# USB.net
KiCad netlist of a schematic drawn in Altium Designer
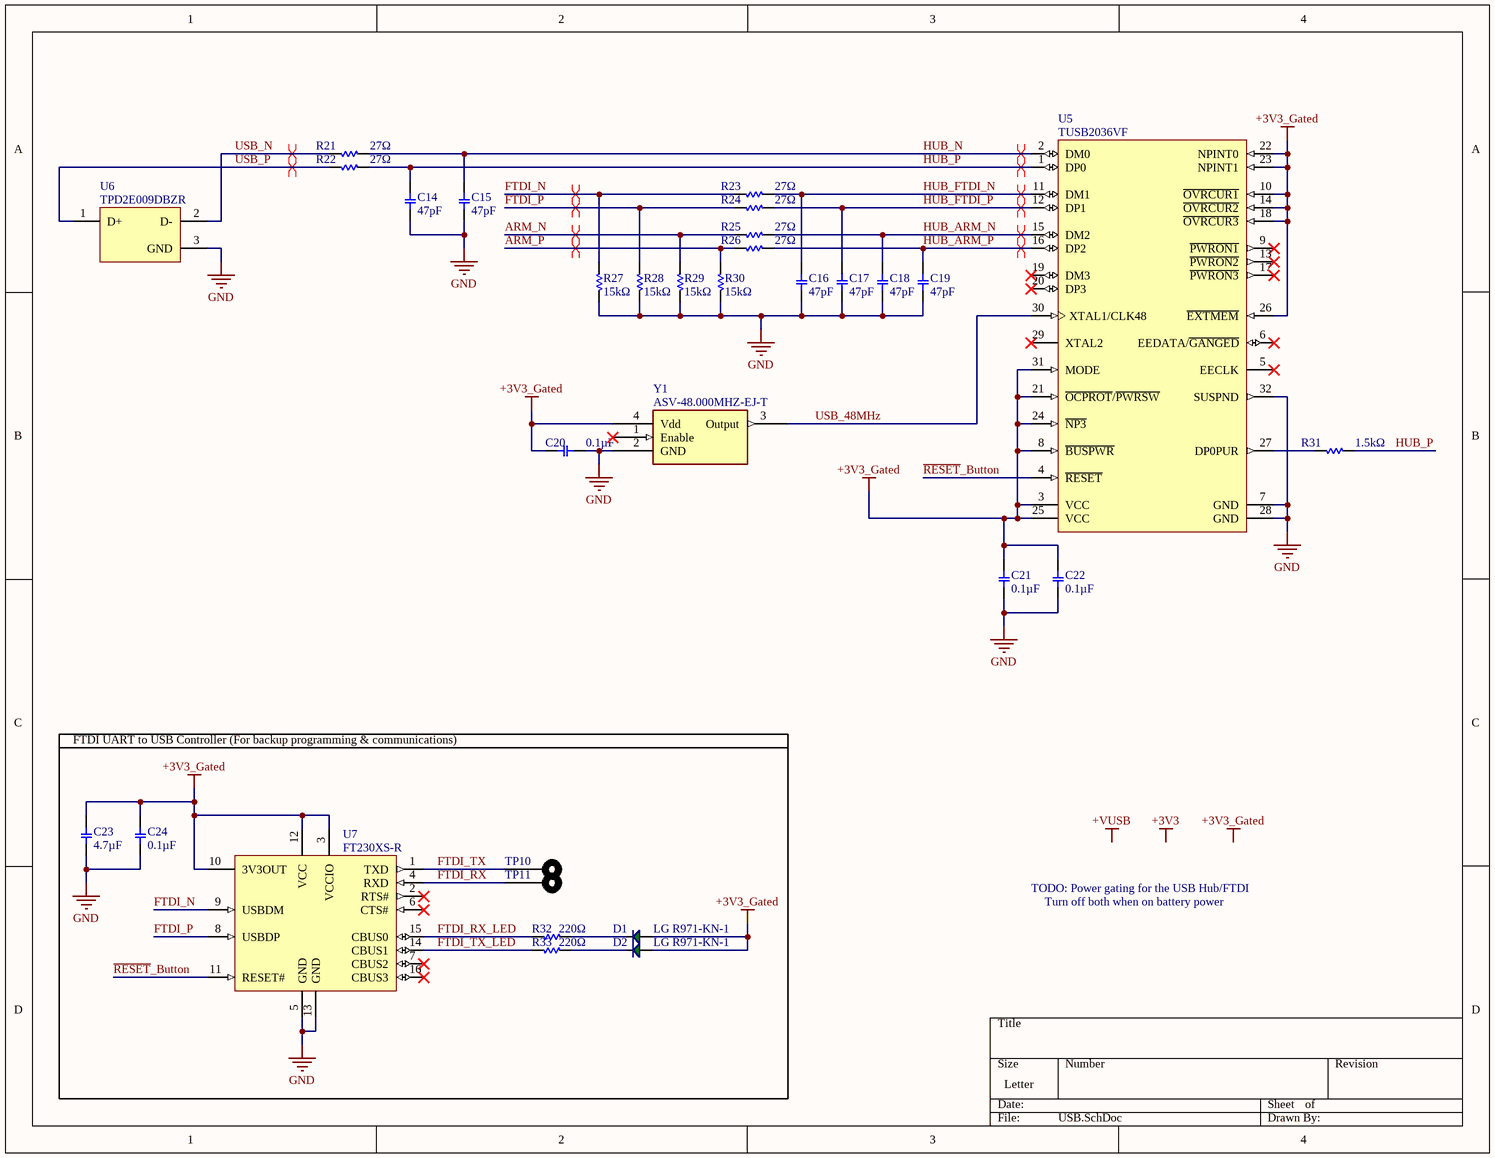
[diagram p0: USB.SchDoc]

(export (version "E")
  (design (tool "Eeschema 10.0.6"))
  (components
    (comp (ref "C14")
      (value "47pF")
      (footprint "C0805(2012)_NP_med")
      (description "SMT Capacitor")
      (fields (field (name "TOLERANCE") "X7R"))
      (libsource (lib "ChipComponents") (part "CPN_SMT"))
    )
    (comp (ref "C15")
      (value "47pF")
      (footprint "C0805(2012)_NP_med")
      (description "SMT Capacitor")
      (fields (field (name "TOLERANCE") "X7R"))
      (libsource (lib "ChipComponents") (part "CPN_SMT"))
    )
    (comp (ref "C16")
      (value "47pF")
      (footprint "C0805(2012)_NP_med")
      (description "SMT Capacitor")
      (fields (field (name "TOLERANCE") "X7R"))
      (libsource (lib "ChipComponents") (part "CPN_SMT"))
    )
    (comp (ref "C17")
      (value "47pF")
      (footprint "C0805(2012)_NP_med")
      (description "SMT Capacitor")
      (fields (field (name "TOLERANCE") "X7R"))
      (libsource (lib "ChipComponents") (part "CPN_SMT"))
    )
    (comp (ref "C18")
      (value "47pF")
      (footprint "C0805(2012)_NP_med")
      (description "SMT Capacitor")
      (fields (field (name "TOLERANCE") "X7R"))
      (libsource (lib "ChipComponents") (part "CPN_SMT"))
    )
    (comp (ref "C19")
      (value "47pF")
      (footprint "C0805(2012)_NP_med")
      (description "SMT Capacitor")
      (fields (field (name "TOLERANCE") "X7R"))
      (libsource (lib "ChipComponents") (part "CPN_SMT"))
    )
    (comp (ref "C20")
      (value "0.1µF")
      (footprint "C0805(2012)_NP_med")
      (description "SMT Capacitor")
      (fields (field (name "TOLERANCE") "X7R"))
      (libsource (lib "ChipComponents") (part "CPN_SMT"))
    )
    (comp (ref "C21")
      (value "0.1µF")
      (footprint "C0805(2012)_NP_med")
      (description "SMT Capacitor")
      (fields (field (name "TOLERANCE") "X7R"))
      (libsource (lib "ChipComponents") (part "CPN_SMT"))
    )
    (comp (ref "C22")
      (value "0.1µF")
      (footprint "C0805(2012)_NP_med")
      (description "SMT Capacitor")
      (fields (field (name "TOLERANCE") "X7R"))
      (libsource (lib "ChipComponents") (part "CPN_SMT"))
    )
    (comp (ref "C23")
      (value "4.7µF")
      (footprint "C0805(2012)_NP_med")
      (description "SMT Capacitor")
      (fields (field (name "TOLERANCE") "X7R"))
      (libsource (lib "ChipComponents") (part "CPN_SMT"))
    )
    (comp (ref "C24")
      (value "0.1µF")
      (footprint "C0805(2012)_NP_med")
      (description "SMT Capacitor")
      (fields (field (name "TOLERANCE") "X7R"))
      (libsource (lib "ChipComponents") (part "CPN_SMT"))
    )
    (comp (ref "D1")
      (value "LG R971-KN-1")
      (footprint "C0805(2012)_P_med")
      (description "SMT LED")
      (fields (field (name "MANUFACTURER") "AVX") (field (name "PART NUMBER") "SD0805S020S1R0"))
      (libsource (lib "ChipComponents") (part "DIODE_sMT"))
    )
    (comp (ref "D2")
      (value "LG R971-KN-1")
      (footprint "C0805(2012)_P_med")
      (description "SMT LED")
      (fields (field (name "MANUFACTURER") "AVX") (field (name "PART NUMBER") "SD0805S020S1R0"))
      (libsource (lib "ChipComponents") (part "DIODE_sMT"))
    )
    (comp (ref "R21")
      (value "27Ω")
      (footprint "R0805(2012)_med")
      (description "SMT resistor")
      (fields (field (name "TOLERANCE") "1%"))
      (libsource (lib "ChipComponents") (part "RES_SMT"))
    )
    (comp (ref "R22")
      (value "27Ω")
      (footprint "R0805(2012)_med")
      (description "SMT resistor")
      (fields (field (name "TOLERANCE") "1%"))
      (libsource (lib "ChipComponents") (part "RES_SMT"))
    )
    (comp (ref "R23")
      (value "27Ω")
      (footprint "R0805(2012)_med")
      (description "SMT resistor")
      (fields (field (name "TOLERANCE") "1%"))
      (libsource (lib "ChipComponents") (part "RES_SMT"))
    )
    (comp (ref "R24")
      (value "27Ω")
      (footprint "R0805(2012)_med")
      (description "SMT resistor")
      (fields (field (name "TOLERANCE") "1%"))
      (libsource (lib "ChipComponents") (part "RES_SMT"))
    )
    (comp (ref "R25")
      (value "27Ω")
      (footprint "R0805(2012)_med")
      (description "SMT resistor")
      (fields (field (name "TOLERANCE") "1%"))
      (libsource (lib "ChipComponents") (part "RES_SMT"))
    )
    (comp (ref "R26")
      (value "27Ω")
      (footprint "R0805(2012)_med")
      (description "SMT resistor")
      (fields (field (name "TOLERANCE") "1%"))
      (libsource (lib "ChipComponents") (part "RES_SMT"))
    )
    (comp (ref "R27")
      (value "15kΩ")
      (footprint "R0805(2012)_med")
      (description "SMT resistor")
      (fields (field (name "TOLERANCE") "1%"))
      (libsource (lib "ChipComponents") (part "RES_SMT"))
    )
    (comp (ref "R28")
      (value "15kΩ")
      (footprint "R0805(2012)_med")
      (description "SMT resistor")
      (fields (field (name "TOLERANCE") "1%"))
      (libsource (lib "ChipComponents") (part "RES_SMT"))
    )
    (comp (ref "R29")
      (value "15kΩ")
      (footprint "R0805(2012)_med")
      (description "SMT resistor")
      (fields (field (name "TOLERANCE") "1%"))
      (libsource (lib "ChipComponents") (part "RES_SMT"))
    )
    (comp (ref "R30")
      (value "15kΩ")
      (footprint "R0805(2012)_med")
      (description "SMT resistor")
      (fields (field (name "TOLERANCE") "1%"))
      (libsource (lib "ChipComponents") (part "RES_SMT"))
    )
    (comp (ref "R31")
      (value "1.5kΩ")
      (footprint "R0805(2012)_med")
      (description "SMT resistor")
      (fields (field (name "TOLERANCE") "1%"))
      (libsource (lib "ChipComponents") (part "RES_SMT"))
    )
    (comp (ref "R32")
      (value "220Ω")
      (footprint "R0805(2012)_med")
      (description "SMT resistor")
      (fields (field (name "TOLERANCE") "1%"))
      (libsource (lib "ChipComponents") (part "RES_SMT"))
    )
    (comp (ref "R33")
      (value "220Ω")
      (footprint "R0805(2012)_med")
      (description "SMT resistor")
      (fields (field (name "TOLERANCE") "1%"))
      (libsource (lib "ChipComponents") (part "RES_SMT"))
    )
    (comp (ref "TP10")
      (value "Testpoint")
      (footprint "TESTPOINT")
      (description "A single hole in the board")
      (libsource (lib "RFIDSchematicLibrary") (part "Testpoint"))
    )
    (comp (ref "TP11")
      (value "Testpoint")
      (footprint "TESTPOINT")
      (description "A single hole in the board")
      (libsource (lib "RFIDSchematicLibrary") (part "Testpoint"))
    )
    (comp (ref "U5")
      (value "TUSB2036VF")
      (footprint "VF32_M")
      (fields (field (name "MANUFACTURER") "Texas Instruments"))
      (libsource (lib "Texas Instruments Interface USB") (part "TUSB2036VF"))
    )
    (comp (ref "U6")
      (value "TPD2E009DBZR")
      (footprint "DBZ3_N")
      (fields (field (name "MANUFACTURER") "Texas Instruments"))
      (libsource (lib "TI Interface ESD EMI Protection") (part "TPD2E009DBZR"))
    )
    (comp (ref "U7")
      (value "FT230XS-R")
      (footprint "SSOP-16_M")
      (fields (field (name "MANUFACTURER") "FTDI"))
      (libsource (lib "FTDI FT-X Series") (part "FT230XS-R"))
    )
    (comp (ref "Y1")
      (value "ASV-48.000MHZ-EJ-T")
      (footprint "Abracon ASV XO")
      (description "OSC XO X.000MHZ HCMOS SMD")
      (libsource (lib "RFIDSchematicLibrary") (part "Abacrom ASV Series"))
    )
  )
  (nets
    (net (code "2") (name "+3V3_Gated") (class "Default")
      (node (ref "C20") (pin "1") (pinfunction "1_1") (pintype "passive"))
      (node (ref "C21") (pin "1") (pinfunction "1_1") (pintype "passive"))
      (node (ref "C22") (pin "1") (pinfunction "1_1") (pintype "passive"))
      (node (ref "C23") (pin "1") (pinfunction "1_1") (pintype "passive"))
      (node (ref "C24") (pin "1") (pinfunction "1_1") (pintype "passive"))
      (node (ref "D1") (pin "2") (pinfunction "A_2") (pintype "passive"))
      (node (ref "D2") (pin "2") (pinfunction "A_2") (pintype "passive"))
      (node (ref "U5") (pin "10") (pinfunction "~{OVRCUR1}_10") (pintype "input"))
      (node (ref "U5") (pin "14") (pinfunction "~{OVRCUR2}_14") (pintype "input"))
      (node (ref "U5") (pin "18") (pinfunction "~{OVRCUR3}_18") (pintype "input"))
      (node (ref "U5") (pin "21") (pinfunction "~{OCPROT}/~{PWRSW}_21") (pintype "input"))
      (node (ref "U5") (pin "22") (pinfunction "NPINT0_22") (pintype "input"))
      (node (ref "U5") (pin "23") (pinfunction "NPINT1_23") (pintype "input"))
      (node (ref "U5") (pin "24") (pinfunction "~{NP3}_24") (pintype "input"))
      (node (ref "U5") (pin "25") (pinfunction "VCC_25") (pintype "power_in"))
      (node (ref "U5") (pin "26") (pinfunction "~{EXTMEM}_26") (pintype "input"))
      (node (ref "U5") (pin "3") (pinfunction "VCC_3") (pintype "power_in"))
      (node (ref "U5") (pin "31") (pinfunction "MODE_31") (pintype "input"))
      (node (ref "U5") (pin "8") (pinfunction "~{BUSPWR}_8") (pintype "input"))
      (node (ref "U7") (pin "10") (pinfunction "3V3OUT_10") (pintype "power_in"))
      (node (ref "U7") (pin "12") (pinfunction "VCC_12") (pintype "power_in"))
      (node (ref "U7") (pin "3") (pinfunction "VCCIO_3") (pintype "power_in"))
      (node (ref "Y1") (pin "4") (pinfunction "Vdd_4") (pintype "power_in"))
    )
    (net (code "4") (name "/ARM_N") (class "Default")
      (node (ref "R25") (pin "1") (pinfunction "1_1") (pintype "passive"))
      (node (ref "R29") (pin "2") (pinfunction "2_2") (pintype "passive"))
    )
    (net (code "5") (name "/ARM_P") (class "Default")
      (node (ref "R26") (pin "1") (pinfunction "1_1") (pintype "passive"))
      (node (ref "R30") (pin "2") (pinfunction "2_2") (pintype "passive"))
    )
    (net (code "6") (name "/FTDI_N") (class "Default")
      (node (ref "R23") (pin "1") (pinfunction "1_1") (pintype "passive"))
      (node (ref "R27") (pin "2") (pinfunction "2_2") (pintype "passive"))
      (node (ref "U7") (pin "9") (pinfunction "USBDM_9") (pintype "input"))
    )
    (net (code "7") (name "/FTDI_P") (class "Default")
      (node (ref "R24") (pin "1") (pinfunction "1_1") (pintype "passive"))
      (node (ref "R28") (pin "2") (pinfunction "2_2") (pintype "passive"))
      (node (ref "U7") (pin "8") (pinfunction "USBDP_8") (pintype "input"))
    )
    (net (code "8") (name "/FTDI_RX") (class "Default")
      (node (ref "TP11") (pin "1") (pinfunction "1_1") (pintype "passive"))
      (node (ref "U7") (pin "4") (pinfunction "RXD_4") (pintype "input"))
    )
    (net (code "9") (name "/FTDI_RX_LED") (class "Default")
      (node (ref "R32") (pin "2") (pinfunction "2_2") (pintype "passive"))
      (node (ref "U7") (pin "15") (pinfunction "CBUS0_15") (pintype "bidirectional"))
    )
    (net (code "10") (name "/FTDI_TX") (class "Default")
      (node (ref "TP10") (pin "1") (pinfunction "1_1") (pintype "passive"))
      (node (ref "U7") (pin "1") (pinfunction "TXD_1") (pintype "output"))
    )
    (net (code "11") (name "/FTDI_TX_LED") (class "Default")
      (node (ref "R33") (pin "2") (pinfunction "2_2") (pintype "passive"))
      (node (ref "U7") (pin "14") (pinfunction "CBUS1_14") (pintype "bidirectional"))
    )
    (net (code "12") (name "/HUB_ARM_N") (class "Default")
      (node (ref "C18") (pin "1") (pinfunction "1_1") (pintype "passive"))
      (node (ref "R25") (pin "2") (pinfunction "2_2") (pintype "passive"))
      (node (ref "U5") (pin "15") (pinfunction "DM2_15") (pintype "bidirectional"))
    )
    (net (code "13") (name "/HUB_ARM_P") (class "Default")
      (node (ref "C19") (pin "1") (pinfunction "1_1") (pintype "passive"))
      (node (ref "R26") (pin "2") (pinfunction "2_2") (pintype "passive"))
      (node (ref "U5") (pin "16") (pinfunction "DP2_16") (pintype "bidirectional"))
    )
    (net (code "14") (name "/HUB_FTDI_N") (class "Default")
      (node (ref "C16") (pin "1") (pinfunction "1_1") (pintype "passive"))
      (node (ref "R23") (pin "2") (pinfunction "2_2") (pintype "passive"))
      (node (ref "U5") (pin "11") (pinfunction "DM1_11") (pintype "bidirectional"))
    )
    (net (code "15") (name "/HUB_FTDI_P") (class "Default")
      (node (ref "C17") (pin "1") (pinfunction "1_1") (pintype "passive"))
      (node (ref "R24") (pin "2") (pinfunction "2_2") (pintype "passive"))
      (node (ref "U5") (pin "12") (pinfunction "DP1_12") (pintype "bidirectional"))
    )
    (net (code "16") (name "/HUB_N") (class "Default")
      (node (ref "C15") (pin "1") (pinfunction "1_1") (pintype "passive"))
      (node (ref "R21") (pin "2") (pinfunction "2_2") (pintype "passive"))
      (node (ref "U5") (pin "2") (pinfunction "DM0_2") (pintype "bidirectional"))
    )
    (net (code "17") (name "/HUB_P") (class "Default")
      (node (ref "C14") (pin "1") (pinfunction "1_1") (pintype "passive"))
      (node (ref "R22") (pin "2") (pinfunction "2_2") (pintype "passive"))
      (node (ref "R31") (pin "2") (pinfunction "2_2") (pintype "passive"))
      (node (ref "U5") (pin "1") (pinfunction "DP0_1") (pintype "bidirectional"))
    )
    (net (code "18") (name "/USB_48MHz") (class "Default")
      (node (ref "U5") (pin "30") (pinfunction "XTAL1/CLK48_30") (pintype "input"))
      (node (ref "Y1") (pin "3") (pinfunction "Output_3") (pintype "output"))
    )
    (net (code "19") (name "/USB_N") (class "Default")
      (node (ref "R21") (pin "1") (pinfunction "1_1") (pintype "passive"))
      (node (ref "U6") (pin "2") (pinfunction "D-_2") (pintype "passive"))
    )
    (net (code "20") (name "/USB_P") (class "Default")
      (node (ref "R22") (pin "1") (pinfunction "1_1") (pintype "passive"))
      (node (ref "U6") (pin "1") (pinfunction "D+_1") (pintype "passive"))
    )
    (net (code "21") (name "/~{RESET}_Button") (class "Default")
      (node (ref "U5") (pin "4") (pinfunction "~{RESET}_4") (pintype "input"))
      (node (ref "U7") (pin "11") (pinfunction "RESET#_11") (pintype "input"))
    )
    (net (code "22") (name "GND") (class "Default")
      (node (ref "C14") (pin "2") (pinfunction "2_2") (pintype "passive"))
      (node (ref "C15") (pin "2") (pinfunction "2_2") (pintype "passive"))
      (node (ref "C16") (pin "2") (pinfunction "2_2") (pintype "passive"))
      (node (ref "C17") (pin "2") (pinfunction "2_2") (pintype "passive"))
      (node (ref "C18") (pin "2") (pinfunction "2_2") (pintype "passive"))
      (node (ref "C19") (pin "2") (pinfunction "2_2") (pintype "passive"))
      (node (ref "C20") (pin "2") (pinfunction "2_2") (pintype "passive"))
      (node (ref "C21") (pin "2") (pinfunction "2_2") (pintype "passive"))
      (node (ref "C22") (pin "2") (pinfunction "2_2") (pintype "passive"))
      (node (ref "C23") (pin "2") (pinfunction "2_2") (pintype "passive"))
      (node (ref "C24") (pin "2") (pinfunction "2_2") (pintype "passive"))
      (node (ref "R27") (pin "1") (pinfunction "1_1") (pintype "passive"))
      (node (ref "R28") (pin "1") (pinfunction "1_1") (pintype "passive"))
      (node (ref "R29") (pin "1") (pinfunction "1_1") (pintype "passive"))
      (node (ref "R30") (pin "1") (pinfunction "1_1") (pintype "passive"))
      (node (ref "U5") (pin "28") (pinfunction "GND_28") (pintype "power_in"))
      (node (ref "U5") (pin "32") (pinfunction "SUSPND_32") (pintype "output"))
      (node (ref "U5") (pin "7") (pinfunction "GND_7") (pintype "power_in"))
      (node (ref "U6") (pin "3") (pinfunction "GND_3") (pintype "power_in"))
      (node (ref "U7") (pin "13") (pinfunction "GND_13") (pintype "power_in"))
      (node (ref "U7") (pin "5") (pinfunction "GND_5") (pintype "power_in"))
      (node (ref "Y1") (pin "2") (pinfunction "GND_2") (pintype "power_in"))
    )
    (net (code "23") (name "Net-(D1-K)") (class "Default")
      (node (ref "D1") (pin "1") (pinfunction "K_1") (pintype "passive"))
      (node (ref "R32") (pin "1") (pinfunction "1_1") (pintype "passive"))
    )
    (net (code "24") (name "Net-(D2-K)") (class "Default")
      (node (ref "D2") (pin "1") (pinfunction "K_1") (pintype "passive"))
      (node (ref "R33") (pin "1") (pinfunction "1_1") (pintype "passive"))
    )
    (net (code "25") (name "Net-(U5-DP0PUR)") (class "Default")
      (node (ref "R31") (pin "1") (pinfunction "1_1") (pintype "passive"))
      (node (ref "U5") (pin "27") (pinfunction "DP0PUR_27") (pintype "output"))
    )
    (net (code "26") (name "unconnected-(U5-DM3-Pad19)") (class "Default")
      (node (ref "U5") (pin "19") (pinfunction "DM3_19") (pintype "bidirectional+no_connect"))
    )
    (net (code "27") (name "unconnected-(U5-DP3-Pad20)") (class "Default")
      (node (ref "U5") (pin "20") (pinfunction "DP3_20") (pintype "bidirectional+no_connect"))
    )
    (net (code "28") (name "unconnected-(U5-EECLK-Pad5)") (class "Default")
      (node (ref "U5") (pin "5") (pinfunction "EECLK_5") (pintype "tri_state+no_connect"))
    )
    (net (code "29") (name "unconnected-(U5-EEDATA{slash}~{GANGED}-Pad6)") (class "Default")
      (node (ref "U5") (pin "6") (pinfunction "EEDATA/~{GANGED}_6") (pintype "bidirectional+no_connect"))
    )
    (net (code "30") (name "unconnected-(U5-XTAL2-Pad29)") (class "Default")
      (node (ref "U5") (pin "29") (pinfunction "XTAL2_29") (pintype "passive+no_connect"))
    )
    (net (code "31") (name "unconnected-(U5-~{PWRON1}-Pad9)") (class "Default")
      (node (ref "U5") (pin "9") (pinfunction "~{PWRON1}_9") (pintype "output+no_connect"))
    )
    (net (code "32") (name "unconnected-(U5-~{PWRON2}-Pad13)") (class "Default")
      (node (ref "U5") (pin "13") (pinfunction "~{PWRON2}_13") (pintype "output+no_connect"))
    )
    (net (code "33") (name "unconnected-(U5-~{PWRON3}-Pad17)") (class "Default")
      (node (ref "U5") (pin "17") (pinfunction "~{PWRON3}_17") (pintype "output+no_connect"))
    )
    (net (code "34") (name "unconnected-(U7-CBUS2-Pad7)") (class "Default")
      (node (ref "U7") (pin "7") (pinfunction "CBUS2_7") (pintype "bidirectional+no_connect"))
    )
    (net (code "35") (name "unconnected-(U7-CBUS3-Pad16)") (class "Default")
      (node (ref "U7") (pin "16") (pinfunction "CBUS3_16") (pintype "bidirectional+no_connect"))
    )
    (net (code "36") (name "unconnected-(U7-CTS#-Pad6)") (class "Default")
      (node (ref "U7") (pin "6") (pinfunction "CTS#_6") (pintype "input+no_connect"))
    )
    (net (code "37") (name "unconnected-(U7-RTS#-Pad2)") (class "Default")
      (node (ref "U7") (pin "2") (pinfunction "RTS#_2") (pintype "output+no_connect"))
    )
    (net (code "38") (name "unconnected-(Y1-Enable-Pad1)") (class "Default")
      (node (ref "Y1") (pin "1") (pinfunction "Enable_1") (pintype "input+no_connect"))
    )
  )
)
